# 08_nRF_RAM.net
KiCad netlist of a schematic drawn in Altium Designer
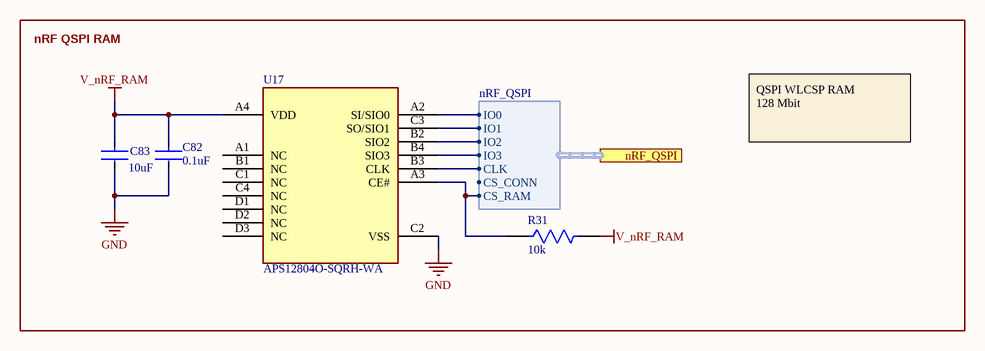
[diagram p0: 08_nRF_RAM.SchDoc]

(export (version "E")
  (design (tool "Eeschema 10.0.6"))
  (components
    (comp (ref "C82")
      (value "GRM033Z71C104KE14D")
      (footprint "FP-GRM033-0_03-IPC_C")
      (description "Chip Multilayer Ceramic Capacitors for General Purpose, 0201, 0.10uF, X7R, 15%, 10%, 16V")
      (fields (field (name "CAPACITANCE") "0.1uF"))
      (libsource (lib "Altium Content Vault") (part "b4654b650e69147ec39a6b967a45e02"))
    )
    (comp (ref "C83")
      (value "CL05A106MP5NUNC")
      (footprint "FP-CL05A106MP5NUNC-IPC_C")
      (description "CAP CER 10UF 10V X5R 0402")
      (fields
        (field (name "OCTOPART") "https://octopart.com/cl05a106mp5nunc-samsung-22457395")
        (field (name "TOLERANCE") "20%")
        (field (name "CAPACITANCE") "10uF")
      )
      (libsource (lib "Altium Content Vault") (part "b4654b650e69147ec39a6b967a45e02"))
    )
    (comp (ref "R31")
      (value "RMCF0201FT10K0")
      (footprint "FP-RMCF0201-IPC_C")
      (description "RES 10K OHM 1% 1/20W 0201")
      (fields (field (name "RESISTANCE") "10k") (field (name "TOLERANCE") "1%"))
      (libsource (lib "Altium Content Vault") (part "1029c3af85768c4190bb7ad29bc67b5"))
    )
    (comp (ref "U17")
      (value "APS12804O-SQRH-WA")
      (footprint "EEG_PcbLib:APS12804O-SQRH-WA")
      (description "QSPI PSRAM in WLCSP package\r\n144 MHz\r\n128 Mbit")
      (libsource (lib "EEG_SchLib") (part "APS12804O-SQRH-WA"))
    )
  )
  (nets
    (net (code "2") (name "/CLK") (class "Default")
      (node (ref "U17") (pin "B3") (pinfunction "CLK_B3") (pintype "passive"))
    )
    (net (code "3") (name "/CS_RAM") (class "Default")
      (node (ref "R31") (pin "1") (pinfunction "1_1") (pintype "passive"))
      (node (ref "U17") (pin "A3") (pinfunction "CE#_A3") (pintype "passive"))
    )
    (net (code "4") (name "/IO0") (class "Default")
      (node (ref "U17") (pin "A2") (pinfunction "SI/SIO0_A2") (pintype "passive"))
    )
    (net (code "5") (name "/IO1") (class "Default")
      (node (ref "U17") (pin "C3") (pinfunction "SO/SIO1_C3") (pintype "passive"))
    )
    (net (code "6") (name "/IO2") (class "Default")
      (node (ref "U17") (pin "B2") (pinfunction "SIO2_B2") (pintype "passive"))
    )
    (net (code "7") (name "/IO3") (class "Default")
      (node (ref "U17") (pin "B4") (pinfunction "SIO3_B4") (pintype "passive"))
    )
    (net (code "9") (name "GND") (class "Default")
      (node (ref "C82") (pin "2") (pinfunction "2_2") (pintype "passive"))
      (node (ref "C83") (pin "2") (pinfunction "2_2") (pintype "passive"))
      (node (ref "U17") (pin "C2") (pinfunction "VSS_C2") (pintype "passive"))
    )
    (net (code "10") (name "V_nRF_RAM") (class "Default")
      (node (ref "C82") (pin "1") (pinfunction "1_1") (pintype "passive"))
      (node (ref "C83") (pin "1") (pinfunction "1_1") (pintype "passive"))
      (node (ref "R31") (pin "2") (pinfunction "2_2") (pintype "passive"))
      (node (ref "U17") (pin "A4") (pinfunction "VDD_A4") (pintype "passive"))
    )
    (net (code "11") (name "unconnected-(U17-NC-PadA1)") (class "Default")
      (node (ref "U17") (pin "A1") (pinfunction "NC_A1") (pintype "passive"))
    )
    (net (code "12") (name "unconnected-(U17-NC-PadB1)") (class "Default")
      (node (ref "U17") (pin "B1") (pinfunction "NC_B1") (pintype "passive"))
    )
    (net (code "13") (name "unconnected-(U17-NC-PadC1)") (class "Default")
      (node (ref "U17") (pin "C1") (pinfunction "NC_C1") (pintype "passive"))
    )
    (net (code "14") (name "unconnected-(U17-NC-PadC4)") (class "Default")
      (node (ref "U17") (pin "C4") (pinfunction "NC_C4") (pintype "passive"))
    )
    (net (code "15") (name "unconnected-(U17-NC-PadD1)") (class "Default")
      (node (ref "U17") (pin "D1") (pinfunction "NC_D1") (pintype "passive"))
    )
    (net (code "16") (name "unconnected-(U17-NC-PadD2)") (class "Default")
      (node (ref "U17") (pin "D2") (pinfunction "NC_D2") (pintype "passive"))
    )
    (net (code "17") (name "unconnected-(U17-NC-PadD3)") (class "Default")
      (node (ref "U17") (pin "D3") (pinfunction "NC_D3") (pintype "passive"))
    )
  )
)
